# homeKit_HumC.net
KiCad netlist of a schematic drawn in EasyEDA Pro
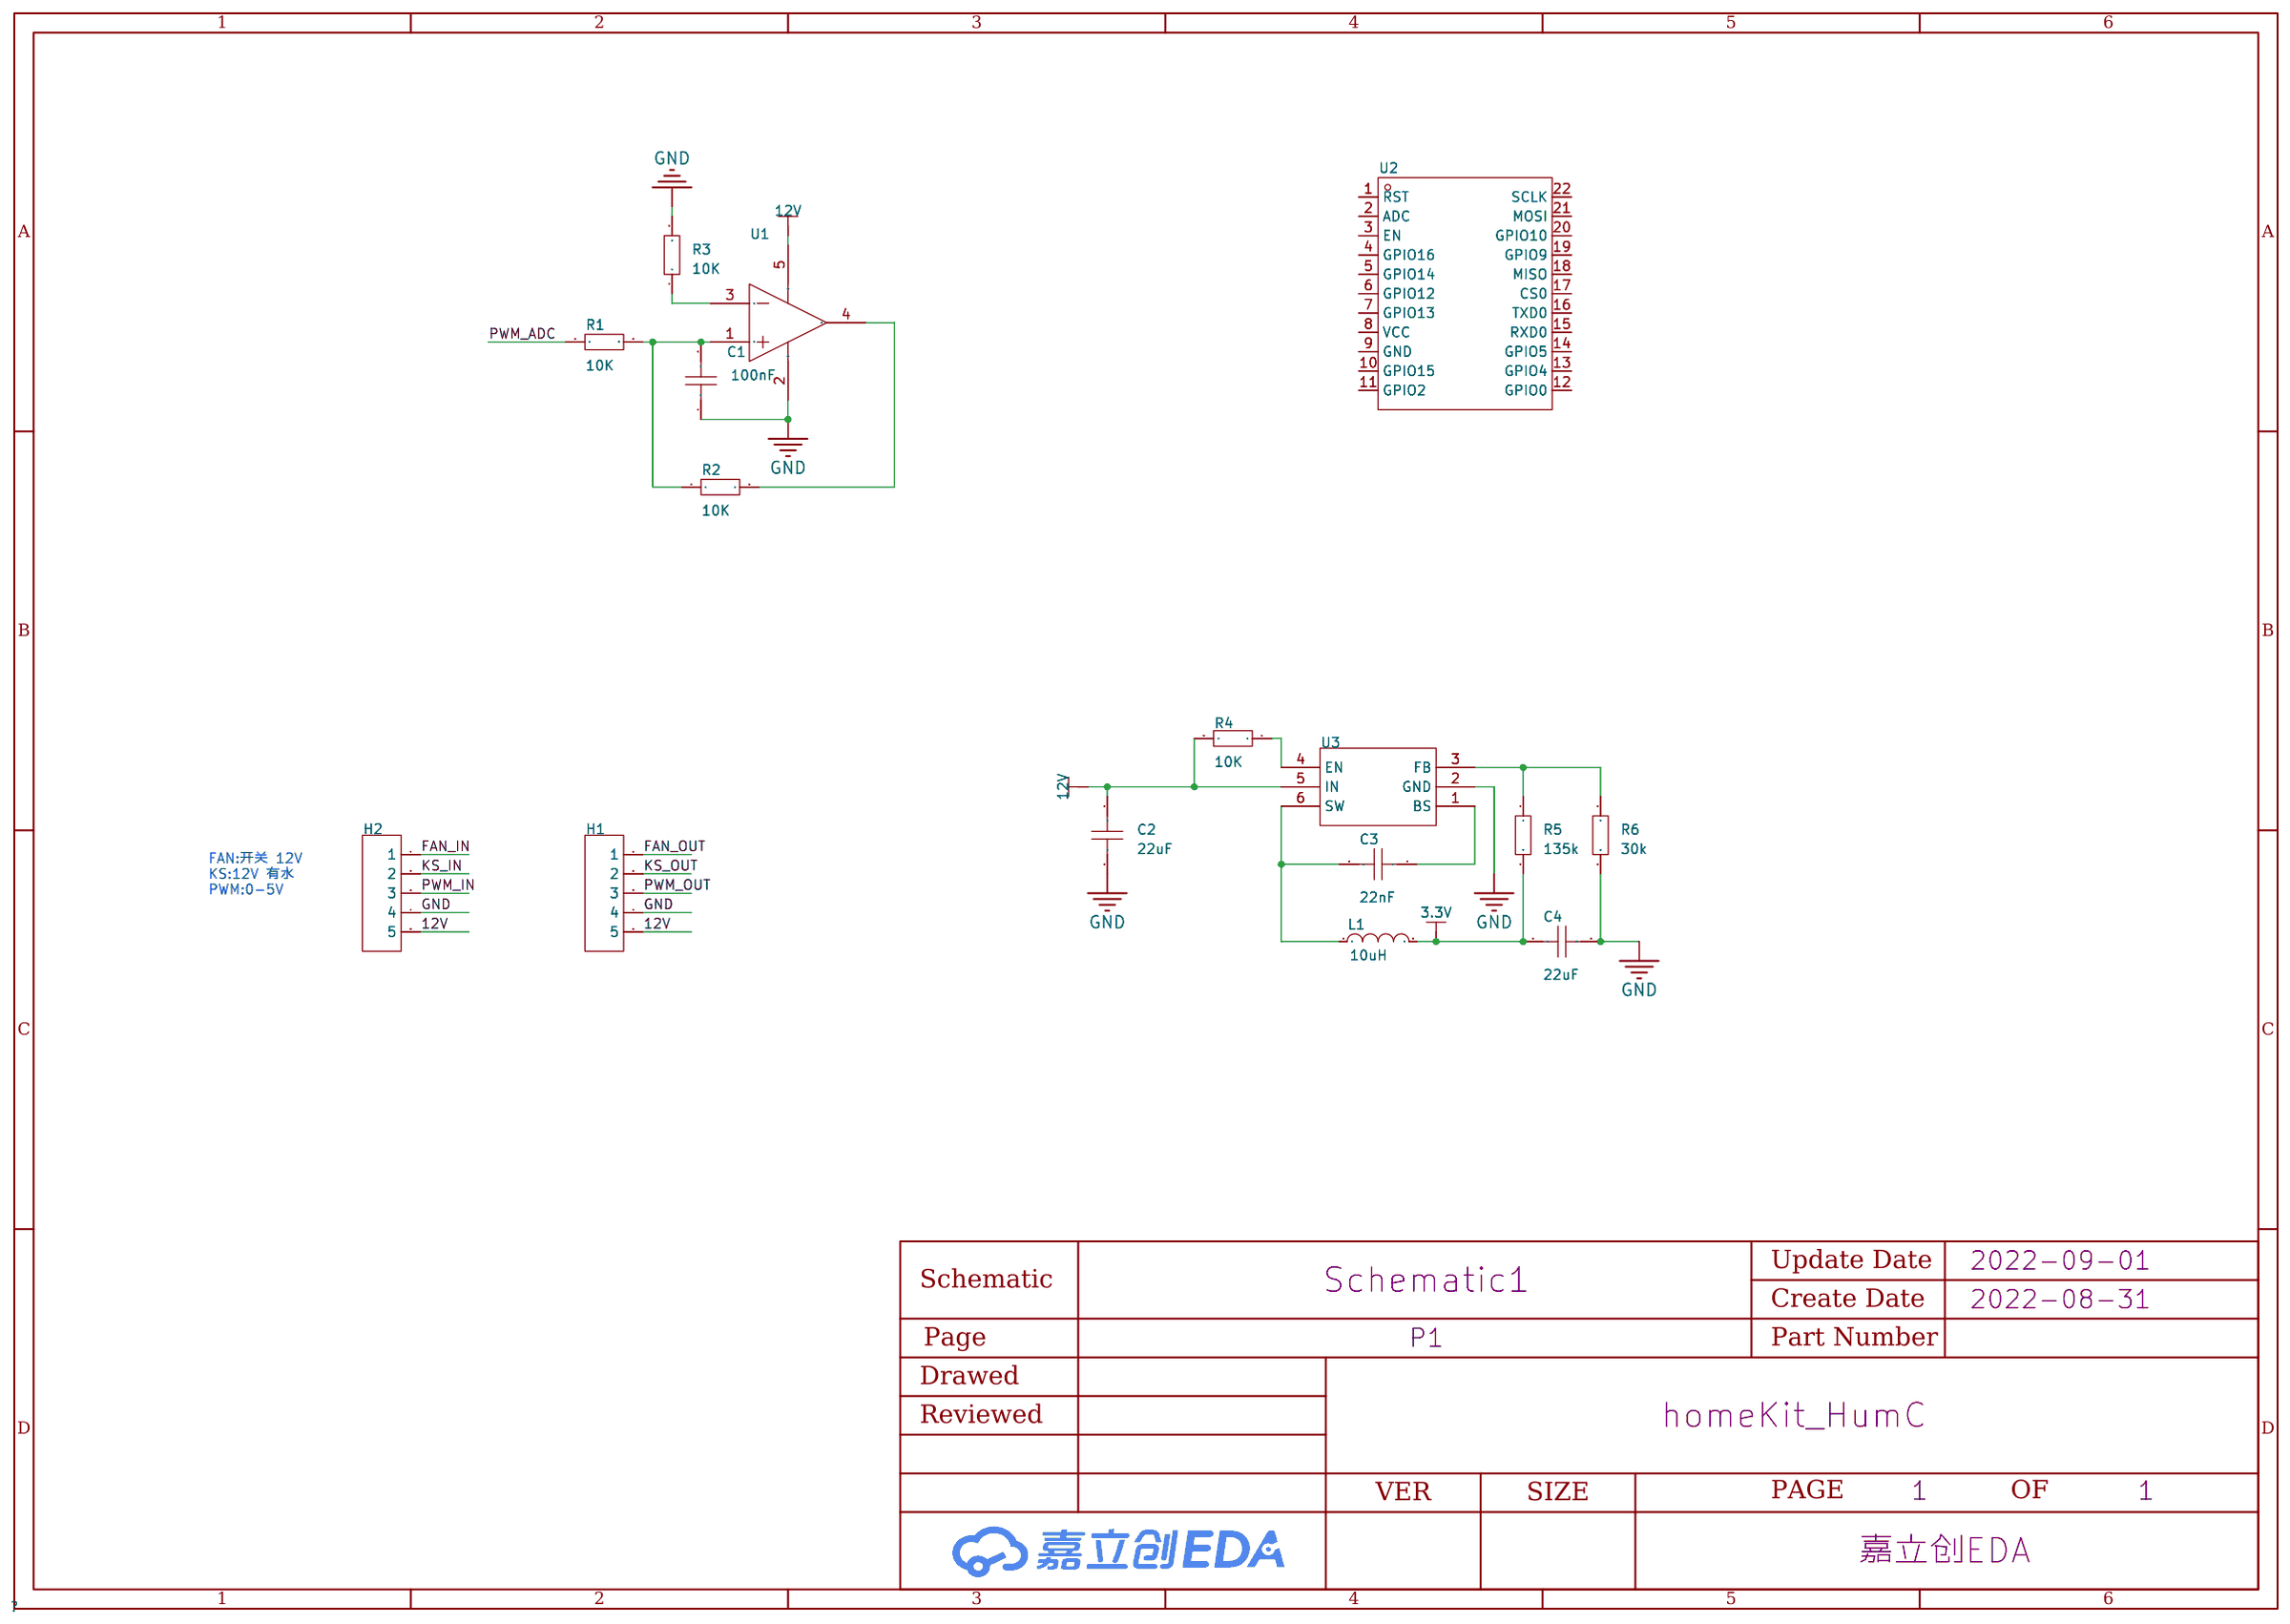
[diagram p0: schematic sheet]

(export (version "E")
  (design (tool "Eeschema 10.0.6"))
  (components
    (comp (ref "C1")
      (value "100nF")
      (footprint "easyedapro:C0603")
      (description "容值:100nF;精度:±10%;额定电压:50V;温度系数:X7R;")
      (libsource (lib "easyedapro") (part "C1210X7R475K630NT"))
    )
    (comp (ref "C2")
      (value "22uF")
      (footprint "easyedapro:C0603")
      (description "容值:100nF;精度:±10%;额定电压:50V;温度系数:X7R;")
      (libsource (lib "easyedapro") (part "C1210X7R475K630NT"))
    )
    (comp (ref "C3")
      (value "22nF")
      (footprint "easyedapro:C0603")
      (description "容值:100nF;精度:±10%;额定电压:50V;温度系数:X7R;")
      (libsource (lib "easyedapro") (part "C1210X7R475K630NT"))
    )
    (comp (ref "C4")
      (value "22uF")
      (footprint "easyedapro:C0603")
      (description "容值:100nF;精度:±10%;额定电压:50V;温度系数:X7R;")
      (libsource (lib "easyedapro") (part "C1210X7R475K630NT"))
    )
    (comp (ref "H1")
      (value "~")
      (footprint "easyedapro:HDR-TH_5P-P2.54-V-F")
      (libsource (lib "easyedapro") (part "Header-Female-2.54_1x5"))
    )
    (comp (ref "H2")
      (value "~")
      (footprint "easyedapro:HDR-TH_5P-P2.54-V-F")
      (libsource (lib "easyedapro") (part "Header-Female-2.54_1x5"))
    )
    (comp (ref "L1")
      (value "10uH")
      (footprint "easyedapro:IND-SMD_L7.4-W6.6")
      (description "电感值:10uH;精度:±20%;额定电流:4A;饱和电流(Isat):5A;直流电阻(DCR):68mΩ;")
      (fields (field (name "Manufacturer Part") "CKST0603-10uH/M") (field (name "Manufacturer") "CENKER(岑科)"))
      (libsource (lib "easyedapro") (part "CKST0603-10UH/M"))
    )
    (comp (ref "R1") (value "10K") (footprint "easyedapro:R0603") (libsource (lib "easyedapro") (part "电阻")))
    (comp (ref "R2") (value "10K") (footprint "easyedapro:R0603") (libsource (lib "easyedapro") (part "电阻")))
    (comp (ref "R3") (value "10K") (footprint "easyedapro:R0603") (libsource (lib "easyedapro") (part "电阻")))
    (comp (ref "R4") (value "10K") (footprint "easyedapro:R0603") (libsource (lib "easyedapro") (part "电阻")))
    (comp (ref "R5") (value "135k") (footprint "easyedapro:R0603") (libsource (lib "easyedapro") (part "电阻")))
    (comp (ref "R6") (value "30k") (footprint "easyedapro:R0603") (libsource (lib "easyedapro") (part "电阻")))
    (comp (ref "U1")
      (value "LM321")
      (footprint "easyedapro:SOT-23-5_L2.9-W1.6-P0.95-LS2.8-BR")
      (fields (field (name "Manufacturer") "CJ(江苏长电/长晶)"))
      (libsource (lib "easyedapro") (part "LM321_C2829424"))
    )
    (comp (ref "U2")
      (value "ESP-12F(ESP8266MOD)")
      (footprint "easyedapro:WIFIM-SMD_ESP-12F-ESP8266MOD")
      (description "屏蔽罩上的丝印是：ESP8266MOD，ESP8266EX串口WIFI")
      (fields (field (name "Manufacturer") "Ai-Thinker(安信可)"))
      (libsource (lib "easyedapro") (part "ESP-12F(ESP8266MOD)"))
    )
    (comp (ref "U3")
      (value "MT2492")
      (footprint "easyedapro:SOT-23-6_L2.9-W1.6-P0.95-LS2.8-BR")
      (description "功能类型:降压型;同步整流:-;输出通道数:-;拓扑结构:-;输入电压:-;输出电流(最大值):-;开关频率:-;")
      (fields (field (name "Manufacturer") "西安航天民芯"))
      (libsource (lib "easyedapro") (part "MT2492"))
    )
  )
  (nets
    (net (code "1") (name "/FAN_IN") (class "Default")
      (node (ref "H2") (pin "1") (pinfunction "1_1") (pintype "input"))
    )
    (net (code "2") (name "/FAN_OUT") (class "Default")
      (node (ref "H1") (pin "1") (pinfunction "1_1") (pintype "input"))
    )
    (net (code "3") (name "/KS_IN") (class "Default")
      (node (ref "H2") (pin "2") (pinfunction "2_2") (pintype "input"))
    )
    (net (code "4") (name "/KS_OUT") (class "Default")
      (node (ref "H1") (pin "2") (pinfunction "2_2") (pintype "input"))
    )
    (net (code "5") (name "/PWM_ADC") (class "Default")
      (node (ref "R1") (pin "1") (pinfunction "1_1") (pintype "input"))
    )
    (net (code "6") (name "/PWM_IN") (class "Default")
      (node (ref "H2") (pin "3") (pinfunction "3_3") (pintype "input"))
    )
    (net (code "7") (name "/PWM_OUT") (class "Default")
      (node (ref "H1") (pin "3") (pinfunction "3_3") (pintype "input"))
    )
    (net (code "8") (name "3.3V") (class "Default")
      (node (ref "C4") (pin "1") (pinfunction "1_1") (pintype "input"))
      (node (ref "L1") (pin "2") (pinfunction "2_2") (pintype "input"))
      (node (ref "R5") (pin "2") (pinfunction "2_2") (pintype "input"))
    )
    (net (code "9") (name "12V") (class "Default")
      (node (ref "C2") (pin "1") (pinfunction "1_1") (pintype "input"))
      (node (ref "H1") (pin "5") (pinfunction "5_5") (pintype "input"))
      (node (ref "H2") (pin "5") (pinfunction "5_5") (pintype "input"))
      (node (ref "R4") (pin "2") (pinfunction "2_2") (pintype "input"))
      (node (ref "U1") (pin "5") (pinfunction "+VS_5") (pintype "input"))
      (node (ref "U3") (pin "5") (pinfunction "IN_5") (pintype "input"))
    )
    (net (code "10") (name "GND") (class "Default")
      (node (ref "C1") (pin "1") (pinfunction "1_1") (pintype "input"))
      (node (ref "C2") (pin "2") (pinfunction "2_2") (pintype "input"))
      (node (ref "C4") (pin "2") (pinfunction "2_2") (pintype "input"))
      (node (ref "H1") (pin "4") (pinfunction "4_4") (pintype "input"))
      (node (ref "H2") (pin "4") (pinfunction "4_4") (pintype "input"))
      (node (ref "R3") (pin "2") (pinfunction "2_2") (pintype "input"))
      (node (ref "R6") (pin "2") (pinfunction "2_2") (pintype "input"))
      (node (ref "U1") (pin "2") (pinfunction "-VS_2") (pintype "input"))
      (node (ref "U3") (pin "2") (pinfunction "GND_2") (pintype "input"))
    )
    (net (code "11") (name "Net-(U1-+IN)") (class "Default")
      (node (ref "C1") (pin "2") (pinfunction "2_2") (pintype "input"))
      (node (ref "R1") (pin "2") (pinfunction "2_2") (pintype "input"))
      (node (ref "R2") (pin "1") (pinfunction "1_1") (pintype "input"))
      (node (ref "U1") (pin "1") (pinfunction "+IN_1") (pintype "input"))
    )
    (net (code "12") (name "Net-(U1--IN)") (class "Default")
      (node (ref "R3") (pin "1") (pinfunction "1_1") (pintype "input"))
      (node (ref "U1") (pin "3") (pinfunction "-IN_3") (pintype "input"))
    )
    (net (code "13") (name "Net-(U1-OUT)") (class "Default")
      (node (ref "R2") (pin "2") (pinfunction "2_2") (pintype "input"))
      (node (ref "U1") (pin "4") (pinfunction "OUT_4") (pintype "output"))
    )
    (net (code "14") (name "Net-(U3-BS)") (class "Default")
      (node (ref "C3") (pin "1") (pinfunction "1_1") (pintype "input"))
      (node (ref "U3") (pin "1") (pinfunction "BS_1") (pintype "input"))
    )
    (net (code "15") (name "Net-(U3-EN)") (class "Default")
      (node (ref "R4") (pin "1") (pinfunction "1_1") (pintype "input"))
      (node (ref "U3") (pin "4") (pinfunction "EN_4") (pintype "input"))
    )
    (net (code "16") (name "Net-(U3-FB)") (class "Default")
      (node (ref "R5") (pin "1") (pinfunction "1_1") (pintype "input"))
      (node (ref "R6") (pin "1") (pinfunction "1_1") (pintype "input"))
      (node (ref "U3") (pin "3") (pinfunction "FB_3") (pintype "input"))
    )
    (net (code "17") (name "Net-(U3-SW)") (class "Default")
      (node (ref "C3") (pin "2") (pinfunction "2_2") (pintype "input"))
      (node (ref "L1") (pin "1") (pinfunction "1_1") (pintype "input"))
      (node (ref "U3") (pin "6") (pinfunction "SW_6") (pintype "input"))
    )
    (net (code "18") (name "unconnected-(U2-ADC-Pad2)") (class "Default")
      (node (ref "U2") (pin "2") (pinfunction "ADC_2") (pintype "input"))
    )
    (net (code "19") (name "unconnected-(U2-CS0-Pad17)") (class "Default")
      (node (ref "U2") (pin "17") (pinfunction "CS0_17") (pintype "input"))
    )
    (net (code "20") (name "unconnected-(U2-EN-Pad3)") (class "Default")
      (node (ref "U2") (pin "3") (pinfunction "EN_3") (pintype "input"))
    )
    (net (code "21") (name "unconnected-(U2-GND-Pad9)") (class "Default")
      (node (ref "U2") (pin "9") (pinfunction "GND_9") (pintype "input"))
    )
    (net (code "22") (name "unconnected-(U2-GPIO0-Pad12)") (class "Default")
      (node (ref "U2") (pin "12") (pinfunction "GPIO0_12") (pintype "input"))
    )
    (net (code "23") (name "unconnected-(U2-GPIO2-Pad11)") (class "Default")
      (node (ref "U2") (pin "11") (pinfunction "GPIO2_11") (pintype "input"))
    )
    (net (code "24") (name "unconnected-(U2-GPIO4-Pad13)") (class "Default")
      (node (ref "U2") (pin "13") (pinfunction "GPIO4_13") (pintype "input"))
    )
    (net (code "25") (name "unconnected-(U2-GPIO5-Pad14)") (class "Default")
      (node (ref "U2") (pin "14") (pinfunction "GPIO5_14") (pintype "input"))
    )
    (net (code "26") (name "unconnected-(U2-GPIO9-Pad19)") (class "Default")
      (node (ref "U2") (pin "19") (pinfunction "GPIO9_19") (pintype "input"))
    )
    (net (code "27") (name "unconnected-(U2-GPIO10-Pad20)") (class "Default")
      (node (ref "U2") (pin "20") (pinfunction "GPIO10_20") (pintype "input"))
    )
    (net (code "28") (name "unconnected-(U2-GPIO12-Pad6)") (class "Default")
      (node (ref "U2") (pin "6") (pinfunction "GPIO12_6") (pintype "input"))
    )
    (net (code "29") (name "unconnected-(U2-GPIO13-Pad7)") (class "Default")
      (node (ref "U2") (pin "7") (pinfunction "GPIO13_7") (pintype "input"))
    )
    (net (code "30") (name "unconnected-(U2-GPIO14-Pad5)") (class "Default")
      (node (ref "U2") (pin "5") (pinfunction "GPIO14_5") (pintype "input"))
    )
    (net (code "31") (name "unconnected-(U2-GPIO15-Pad10)") (class "Default")
      (node (ref "U2") (pin "10") (pinfunction "GPIO15_10") (pintype "input"))
    )
    (net (code "32") (name "unconnected-(U2-GPIO16-Pad4)") (class "Default")
      (node (ref "U2") (pin "4") (pinfunction "GPIO16_4") (pintype "input"))
    )
    (net (code "33") (name "unconnected-(U2-MISO-Pad18)") (class "Default")
      (node (ref "U2") (pin "18") (pinfunction "MISO_18") (pintype "input"))
    )
    (net (code "34") (name "unconnected-(U2-MOSI-Pad21)") (class "Default")
      (node (ref "U2") (pin "21") (pinfunction "MOSI_21") (pintype "input"))
    )
    (net (code "35") (name "unconnected-(U2-RST-Pad1)") (class "Default")
      (node (ref "U2") (pin "1") (pinfunction "RST_1") (pintype "input"))
    )
    (net (code "36") (name "unconnected-(U2-RXD0-Pad15)") (class "Default")
      (node (ref "U2") (pin "15") (pinfunction "RXD0_15") (pintype "input"))
    )
    (net (code "37") (name "unconnected-(U2-SCLK-Pad22)") (class "Default")
      (node (ref "U2") (pin "22") (pinfunction "SCLK_22") (pintype "input"))
    )
    (net (code "38") (name "unconnected-(U2-TXD0-Pad16)") (class "Default")
      (node (ref "U2") (pin "16") (pinfunction "TXD0_16") (pintype "input"))
    )
    (net (code "39") (name "unconnected-(U2-VCC-Pad8)") (class "Default")
      (node (ref "U2") (pin "8") (pinfunction "VCC_8") (pintype "input"))
    )
  )
)
